# Sheet1.net
KiCad netlist of a schematic drawn in Altium Designer
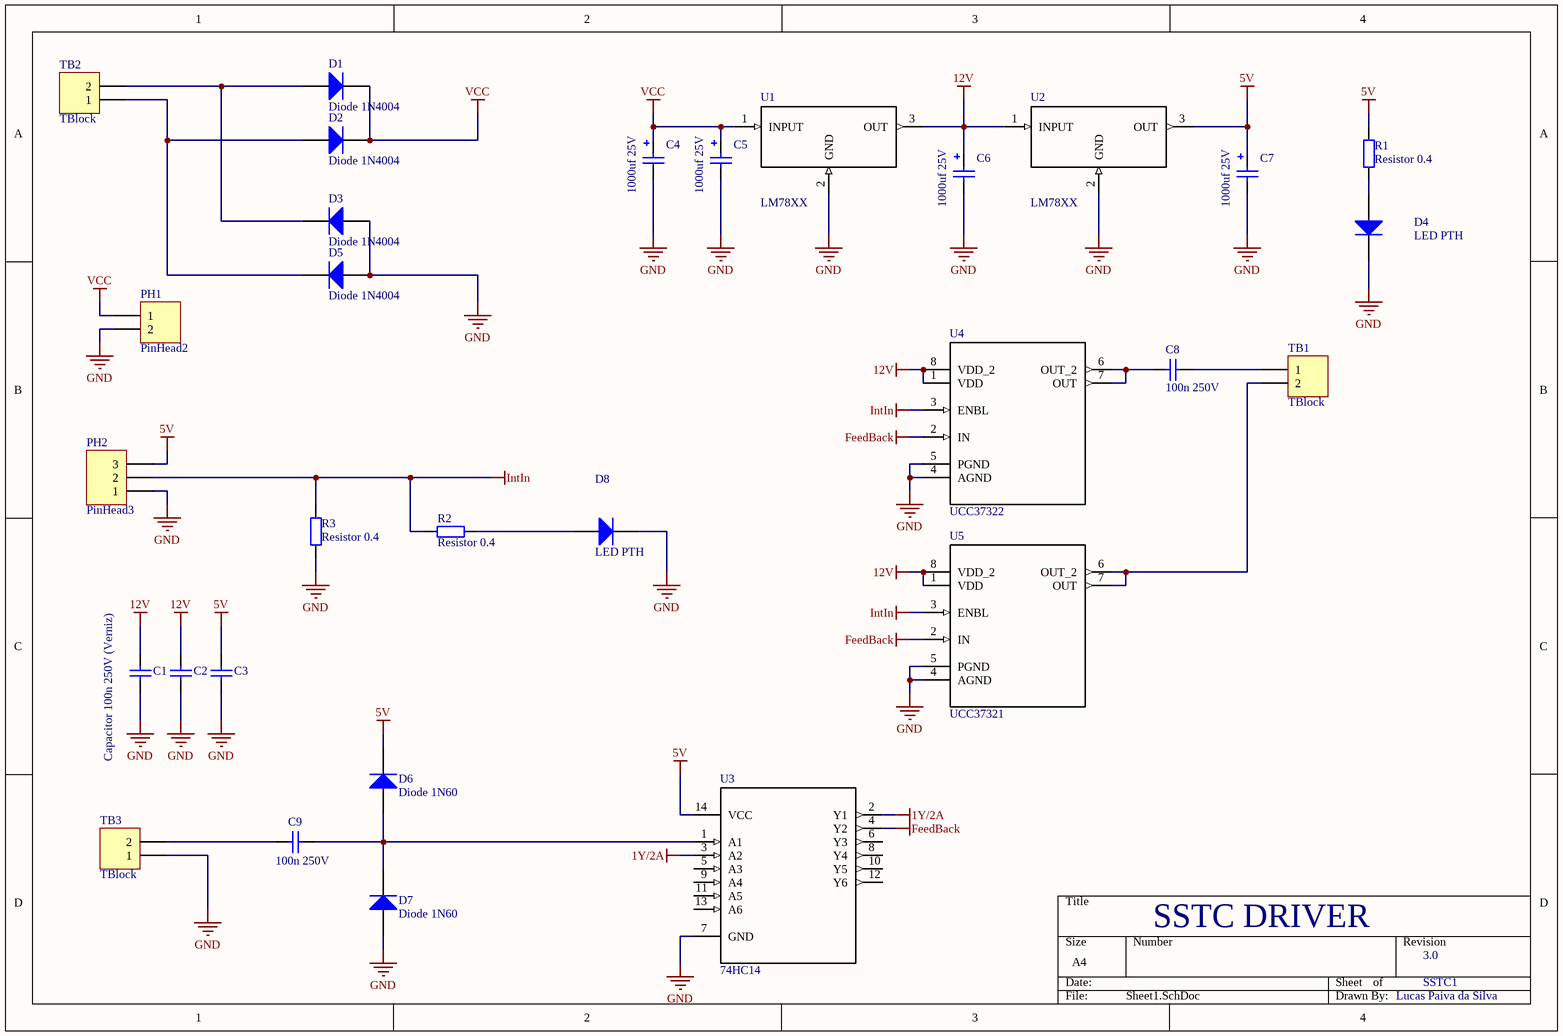
[diagram p0: Sheet1.SchDoc]

(export (version "E")
  (design (tool "Eeschema 10.0.6"))
  (components
    (comp (ref "C1")
      (value "Capacitor 100n 250V (Verniz)")
      (footprint "Capacitor 100n (cor verniz)")
      (libsource (lib "SPaivachlib1") (part "Capacitor 100n 250V (Verniz)"))
    )
    (comp (ref "C2")
      (value "Capacitor 100n 250V (Verniz)")
      (footprint "Capacitor 100n (cor verniz)")
      (libsource (lib "SPaivachlib1") (part "Capacitor 100n 250V (Verniz)"))
    )
    (comp (ref "C3")
      (value "Capacitor 100n 250V (Verniz)")
      (footprint "Capacitor 100n (cor verniz)")
      (libsource (lib "SPaivachlib1") (part "Capacitor 100n 250V (Verniz)"))
    )
    (comp (ref "C4")
      (value "1000uf 25V")
      (footprint "Capacitor 1000u 25V")
      (libsource (lib "SPaivachlib1") (part "Capacitor 1000uf 25V"))
    )
    (comp (ref "C5")
      (value "1000uf 25V")
      (footprint "Capacitor 1000u 25V")
      (libsource (lib "SPaivachlib1") (part "Capacitor 1000uf 25V"))
    )
    (comp (ref "C6")
      (value "1000uf 25V")
      (footprint "Capacitor 1000u 25V")
      (libsource (lib "SPaivachlib1") (part "Capacitor 1000uf 25V"))
    )
    (comp (ref "C7")
      (value "1000uf 25V")
      (footprint "Capacitor 1000u 25V")
      (libsource (lib "SPaivachlib1") (part "Capacitor 1000uf 25V"))
    )
    (comp (ref "C8")
      (value "100n 250V")
      (footprint "Capacitor 100n (cor verniz)")
      (libsource (lib "SPaivachlib1") (part "Capacitor 100n 250V (Verniz)"))
    )
    (comp (ref "C9")
      (value "100n 250V")
      (footprint "Capacitor 100n (cor verniz)")
      (libsource (lib "SPaivachlib1") (part "Capacitor 100n 250V (Verniz)"))
    )
    (comp (ref "D1")
      (value "Diode 1N4004")
      (footprint "Diode 0.4")
      (libsource (lib "SPaivachlib1") (part "Diode 1N4004"))
    )
    (comp (ref "D2")
      (value "Diode 1N4004")
      (footprint "Diode 0.4")
      (libsource (lib "SPaivachlib1") (part "Diode 1N4004"))
    )
    (comp (ref "D3")
      (value "Diode 1N4004")
      (footprint "Diode 0.4")
      (libsource (lib "SPaivachlib1") (part "Diode 1N4004"))
    )
    (comp (ref "D4")
      (value "LED PTH")
      (footprint "LED PTH")
      (libsource (lib "SPaivachlib1") (part "LED PTH"))
    )
    (comp (ref "D5")
      (value "Diode 1N4004")
      (footprint "Diode 0.4")
      (libsource (lib "SPaivachlib1") (part "Diode 1N4004"))
    )
    (comp (ref "D6")
      (value "Diode 1N60")
      (footprint "Diode 0.4")
      (libsource (lib "SPaivachlib1") (part "Diode 1N4004"))
    )
    (comp (ref "D7")
      (value "Diode 1N60")
      (footprint "Diode 0.4")
      (libsource (lib "SPaivachlib1") (part "Diode 1N4004"))
    )
    (comp (ref "D8")
      (value "LED PTH")
      (footprint "LED PTH")
      (libsource (lib "SPaivachlib1") (part "LED PTH"))
    )
    (comp (ref "PH1")
      (value "PinHead2")
      (footprint "PinHead2")
      (libsource (lib "SPaivachlib1") (part "PinHead2"))
    )
    (comp (ref "PH2")
      (value "PinHead3")
      (footprint "PINHEAD3")
      (libsource (lib "SPaivachlib1") (part "PinHead3"))
    )
    (comp (ref "R1")
      (value "Resistor 0.4")
      (footprint "Resistor Axial 0.4")
      (libsource (lib "SPaivachlib1") (part "Resistor 0.4"))
    )
    (comp (ref "R2")
      (value "Resistor 0.4")
      (footprint "Resistor Axial 0.4")
      (libsource (lib "") (part "Resistor 0.4_1"))
    )
    (comp (ref "R3")
      (value "Resistor 0.4")
      (footprint "Resistor Axial 0.4")
      (libsource (lib "SPaivachlib1") (part "Resistor 0.4"))
    )
    (comp (ref "TB1") (value "TBlock") (footprint "TBlock") (libsource (lib "SPaivachlib1") (part "TBlock")))
    (comp (ref "TB2") (value "TBlock") (footprint "TBlock") (libsource (lib "") (part "TBlock_1")))
    (comp (ref "TB3") (value "TBlock") (footprint "TBlock") (libsource (lib "") (part "TBlock_1")))
    (comp (ref "U1")
      (value "LM78XX")
      (footprint "LM317/337")
      (libsource (lib "SPaivachlib1") (part "LM78XX"))
    )
    (comp (ref "U2")
      (value "LM78XX")
      (footprint "LM317/337")
      (libsource (lib "SPaivachlib1") (part "LM78XX"))
    )
    (comp (ref "U3") (value "74HC14") (footprint "74HC14") (libsource (lib "SPaivachlib1") (part "74HC14")))
    (comp (ref "U4")
      (value "UCC37322")
      (footprint "UCC37322/21")
      (libsource (lib "SPaivachlib1") (part "UCC37322"))
    )
    (comp (ref "U5")
      (value "UCC37321")
      (footprint "UCC37322/21")
      (libsource (lib "SPaivachlib1") (part "UCC37321"))
    )
  )
  (nets
    (net (code "1") (name "1Y{slash}2A") (class "Default")
      (node (ref "U3") (pin "2") (pinfunction "Y1_2") (pintype "output"))
      (node (ref "U3") (pin "3") (pinfunction "A2_3") (pintype "input"))
    )
    (net (code "2") (name "5V") (class "Default")
      (node (ref "C3") (pin "2") (pinfunction "2_2") (pintype "passive"))
      (node (ref "C7") (pin "2") (pinfunction "2_2") (pintype "passive"))
      (node (ref "D6") (pin "K") (pinfunction "K_K") (pintype "passive"))
      (node (ref "PH2") (pin "3") (pinfunction "3_3") (pintype "passive"))
      (node (ref "R1") (pin "2") (pinfunction "2_2") (pintype "passive"))
      (node (ref "U2") (pin "3") (pinfunction "OUT_3") (pintype "output"))
      (node (ref "U3") (pin "14") (pinfunction "VCC_14") (pintype "power_in"))
    )
    (net (code "3") (name "12V") (class "Default")
      (node (ref "C1") (pin "2") (pinfunction "2_2") (pintype "passive"))
      (node (ref "C2") (pin "2") (pinfunction "2_2") (pintype "passive"))
      (node (ref "C6") (pin "2") (pinfunction "2_2") (pintype "passive"))
      (node (ref "U1") (pin "3") (pinfunction "OUT_3") (pintype "output"))
      (node (ref "U2") (pin "1") (pinfunction "INPUT_1") (pintype "input"))
      (node (ref "U4") (pin "1") (pinfunction "VDD_1") (pintype "power_in"))
      (node (ref "U4") (pin "8") (pinfunction "VDD_2_8") (pintype "power_in"))
      (node (ref "U5") (pin "1") (pinfunction "VDD_1") (pintype "power_in"))
      (node (ref "U5") (pin "8") (pinfunction "VDD_2_8") (pintype "power_in"))
    )
    (net (code "4") (name "FeedBack") (class "Default")
      (node (ref "U3") (pin "4") (pinfunction "Y2_4") (pintype "output"))
      (node (ref "U4") (pin "2") (pinfunction "IN_2") (pintype "input"))
      (node (ref "U5") (pin "2") (pinfunction "IN_2") (pintype "input"))
    )
    (net (code "5") (name "GND") (class "Default")
      (node (ref "C1") (pin "1") (pinfunction "1_1") (pintype "passive"))
      (node (ref "C2") (pin "1") (pinfunction "1_1") (pintype "passive"))
      (node (ref "C3") (pin "1") (pinfunction "1_1") (pintype "passive"))
      (node (ref "C4") (pin "1") (pinfunction "1_1") (pintype "passive"))
      (node (ref "C5") (pin "1") (pinfunction "1_1") (pintype "passive"))
      (node (ref "C6") (pin "1") (pinfunction "1_1") (pintype "passive"))
      (node (ref "C7") (pin "1") (pinfunction "1_1") (pintype "passive"))
      (node (ref "D3") (pin "A") (pinfunction "A_A") (pintype "passive"))
      (node (ref "D4") (pin "2") (pinfunction "K_2") (pintype "passive"))
      (node (ref "D5") (pin "A") (pinfunction "A_A") (pintype "passive"))
      (node (ref "D7") (pin "A") (pinfunction "A_A") (pintype "passive"))
      (node (ref "D8") (pin "2") (pinfunction "K_2") (pintype "passive"))
      (node (ref "PH1") (pin "2") (pinfunction "2_2") (pintype "passive"))
      (node (ref "PH2") (pin "1") (pinfunction "1_1") (pintype "passive"))
      (node (ref "R3") (pin "1") (pinfunction "1_1") (pintype "passive"))
      (node (ref "TB3") (pin "1") (pinfunction "1_1") (pintype "passive"))
      (node (ref "U1") (pin "2") (pinfunction "GND_2") (pintype "input"))
      (node (ref "U2") (pin "2") (pinfunction "GND_2") (pintype "input"))
      (node (ref "U3") (pin "7") (pinfunction "GND_7") (pintype "passive"))
      (node (ref "U4") (pin "4") (pinfunction "AGND_4") (pintype "passive"))
      (node (ref "U4") (pin "5") (pinfunction "PGND_5") (pintype "passive"))
      (node (ref "U5") (pin "4") (pinfunction "AGND_4") (pintype "passive"))
      (node (ref "U5") (pin "5") (pinfunction "PGND_5") (pintype "passive"))
    )
    (net (code "6") (name "IntIn") (class "Default")
      (node (ref "PH2") (pin "2") (pinfunction "2_2") (pintype "passive"))
      (node (ref "R2") (pin "1") (pinfunction "1_1") (pintype "passive"))
      (node (ref "R3") (pin "2") (pinfunction "2_2") (pintype "passive"))
      (node (ref "U4") (pin "3") (pinfunction "ENBL_3") (pintype "input"))
      (node (ref "U5") (pin "3") (pinfunction "ENBL_3") (pintype "input"))
    )
    (net (code "7") (name "Net-(C8-Pad2)") (class "Default")
      (node (ref "C8") (pin "2") (pinfunction "2_2") (pintype "passive"))
      (node (ref "TB1") (pin "1") (pinfunction "1_1") (pintype "passive"))
    )
    (net (code "8") (name "Net-(C9-Pad1)") (class "Default")
      (node (ref "C9") (pin "1") (pinfunction "1_1") (pintype "passive"))
      (node (ref "TB3") (pin "2") (pinfunction "2_2") (pintype "passive"))
    )
    (net (code "9") (name "Net-(D1-PadA)") (class "Default")
      (node (ref "D1") (pin "A") (pinfunction "A_A") (pintype "passive"))
      (node (ref "D3") (pin "K") (pinfunction "K_K") (pintype "passive"))
      (node (ref "TB2") (pin "2") (pinfunction "2_2") (pintype "passive"))
    )
    (net (code "10") (name "Net-(D2-PadA)") (class "Default")
      (node (ref "D2") (pin "A") (pinfunction "A_A") (pintype "passive"))
      (node (ref "D5") (pin "K") (pinfunction "K_K") (pintype "passive"))
      (node (ref "TB2") (pin "1") (pinfunction "1_1") (pintype "passive"))
    )
    (net (code "11") (name "Net-(D4-A)") (class "Default")
      (node (ref "D4") (pin "1") (pinfunction "A_1") (pintype "passive"))
      (node (ref "R1") (pin "1") (pinfunction "1_1") (pintype "passive"))
    )
    (net (code "12") (name "Net-(D8-A)") (class "Default")
      (node (ref "D8") (pin "1") (pinfunction "A_1") (pintype "passive"))
      (node (ref "R2") (pin "2") (pinfunction "2_2") (pintype "passive"))
    )
    (net (code "13") (name "Net-(U3-A1)") (class "Default")
      (node (ref "C9") (pin "2") (pinfunction "2_2") (pintype "passive"))
      (node (ref "D6") (pin "A") (pinfunction "A_A") (pintype "passive"))
      (node (ref "D7") (pin "K") (pinfunction "K_K") (pintype "passive"))
      (node (ref "U3") (pin "1") (pinfunction "A1_1") (pintype "input"))
    )
    (net (code "14") (name "Net-(U4-OUT)") (class "Default")
      (node (ref "C8") (pin "1") (pinfunction "1_1") (pintype "passive"))
      (node (ref "U4") (pin "6") (pinfunction "OUT_2_6") (pintype "output"))
      (node (ref "U4") (pin "7") (pinfunction "OUT_7") (pintype "output"))
    )
    (net (code "15") (name "Net-(U5-OUT)") (class "Default")
      (node (ref "TB1") (pin "2") (pinfunction "2_2") (pintype "passive"))
      (node (ref "U5") (pin "6") (pinfunction "OUT_2_6") (pintype "output"))
      (node (ref "U5") (pin "7") (pinfunction "OUT_7") (pintype "output"))
    )
    (net (code "16") (name "VCC") (class "Default")
      (node (ref "C4") (pin "2") (pinfunction "2_2") (pintype "passive"))
      (node (ref "C5") (pin "2") (pinfunction "2_2") (pintype "passive"))
      (node (ref "D1") (pin "K") (pinfunction "K_K") (pintype "passive"))
      (node (ref "D2") (pin "K") (pinfunction "K_K") (pintype "passive"))
      (node (ref "PH1") (pin "1") (pinfunction "1_1") (pintype "passive"))
      (node (ref "U1") (pin "1") (pinfunction "INPUT_1") (pintype "input"))
    )
    (net (code "17") (name "unconnected-(U3-A3-Pad5)") (class "Default")
      (node (ref "U3") (pin "5") (pinfunction "A3_5") (pintype "input"))
    )
    (net (code "18") (name "unconnected-(U3-A4-Pad9)") (class "Default")
      (node (ref "U3") (pin "9") (pinfunction "A4_9") (pintype "input"))
    )
    (net (code "19") (name "unconnected-(U3-A5-Pad11)") (class "Default")
      (node (ref "U3") (pin "11") (pinfunction "A5_11") (pintype "input"))
    )
    (net (code "20") (name "unconnected-(U3-A6-Pad13)") (class "Default")
      (node (ref "U3") (pin "13") (pinfunction "A6_13") (pintype "input"))
    )
    (net (code "21") (name "unconnected-(U3-Y3-Pad6)") (class "Default")
      (node (ref "U3") (pin "6") (pinfunction "Y3_6") (pintype "output"))
    )
    (net (code "22") (name "unconnected-(U3-Y4-Pad8)") (class "Default")
      (node (ref "U3") (pin "8") (pinfunction "Y4_8") (pintype "output"))
    )
    (net (code "23") (name "unconnected-(U3-Y5-Pad10)") (class "Default")
      (node (ref "U3") (pin "10") (pinfunction "Y5_10") (pintype "output"))
    )
    (net (code "24") (name "unconnected-(U3-Y6-Pad12)") (class "Default")
      (node (ref "U3") (pin "12") (pinfunction "Y6_12") (pintype "output"))
    )
  )
)
